# ne5044_emulator.net
KiCad netlist of a schematic drawn in EAGLE
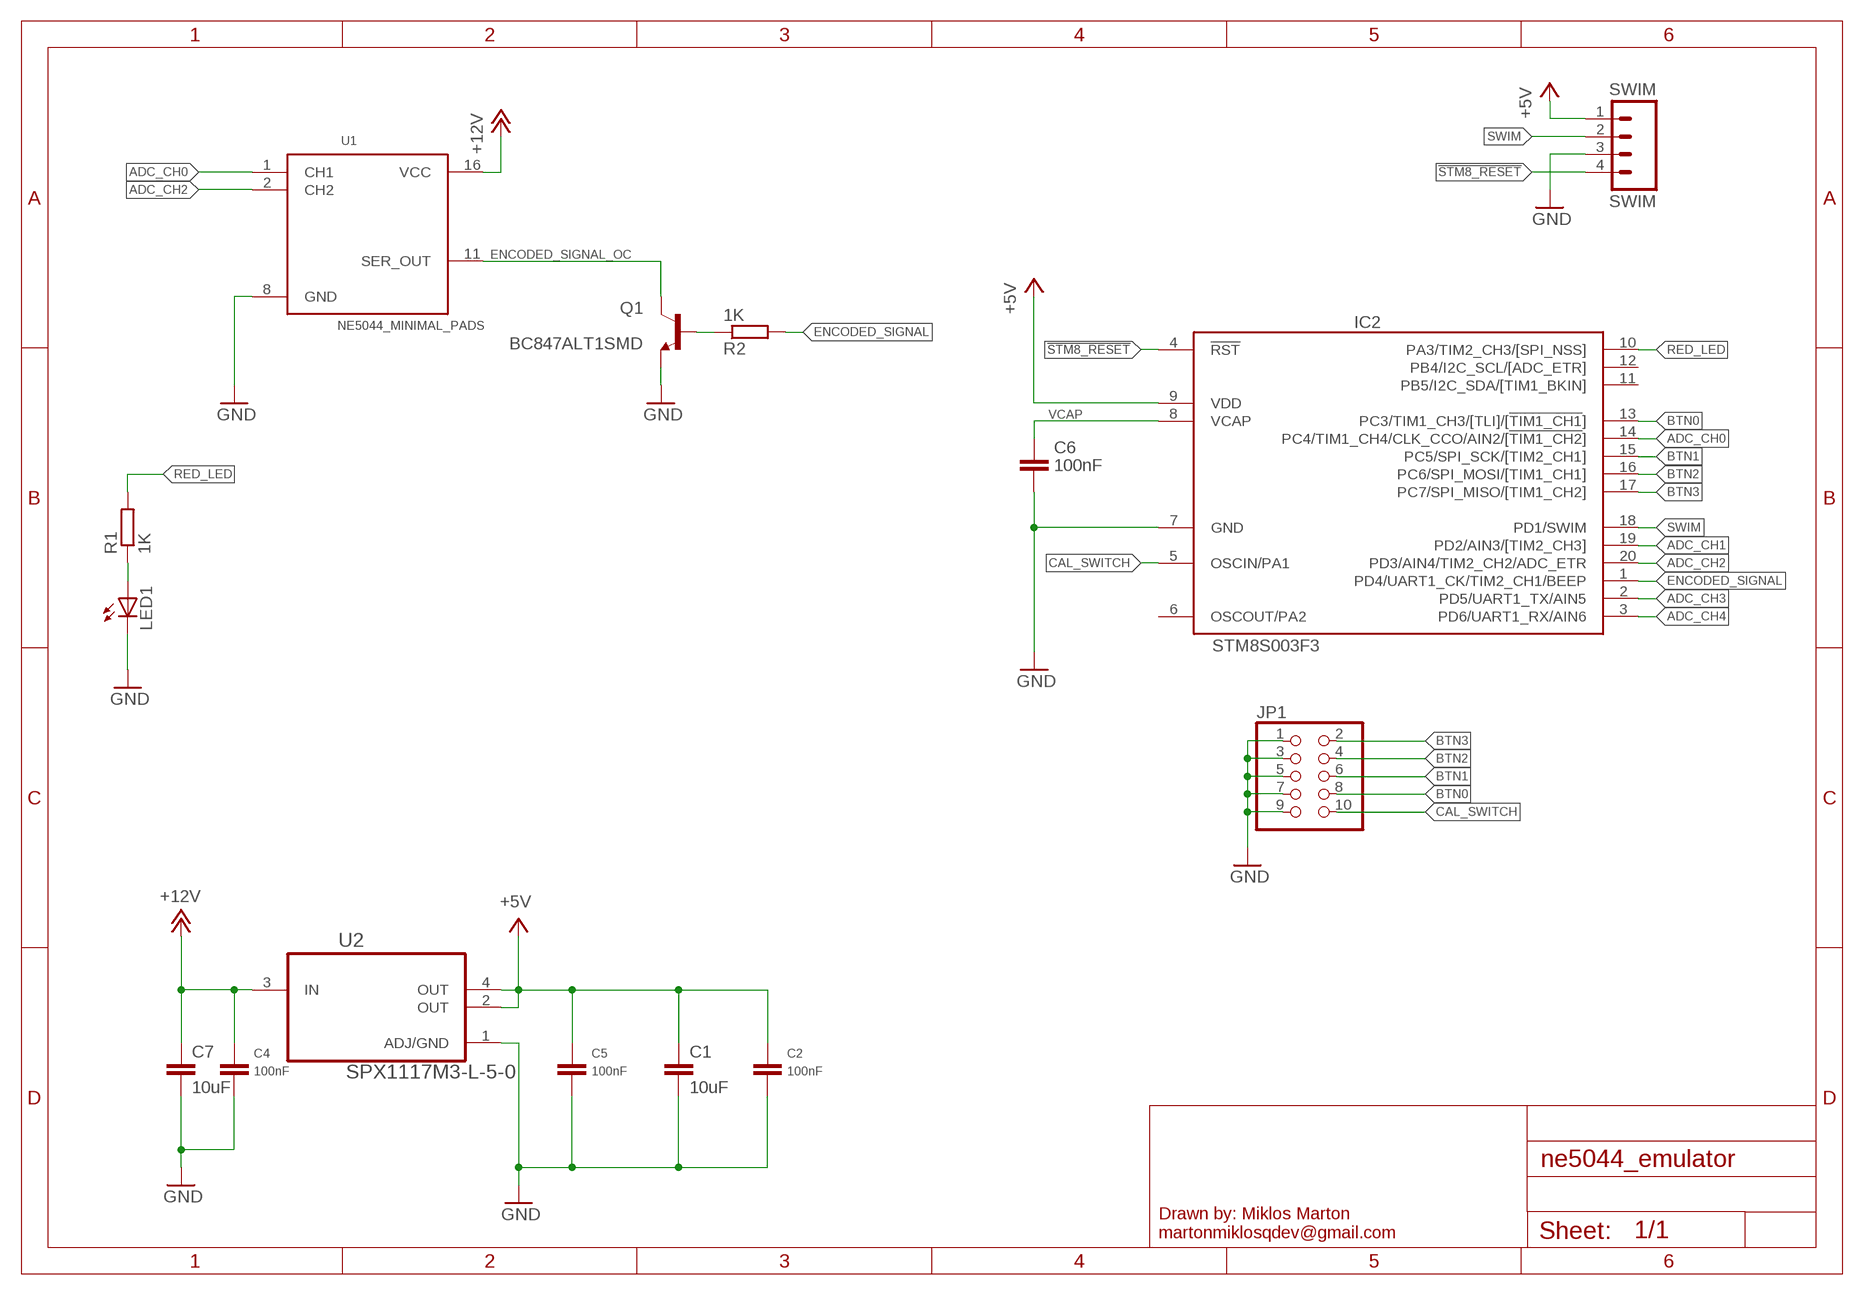
[diagram p0: schematic, sheet 1]

(export (version "E")
  (design (tool "Eeschema 10.0.6"))
  (components
    (comp (ref "C1")
      (value "10uF")
      (footprint "eagle-import:C0805")
      (libsource (lib "eagle-import") (part "C-EUC0805"))
    )
    (comp (ref "C2")
      (value "100nF")
      (footprint "eagle-import:C0603K")
      (libsource (lib "eagle-import") (part "C-EUC0603K"))
    )
    (comp (ref "C4")
      (value "100nF")
      (footprint "eagle-import:C0603K")
      (libsource (lib "eagle-import") (part "C-EUC0603K"))
    )
    (comp (ref "C5")
      (value "100nF")
      (footprint "eagle-import:C0603K")
      (libsource (lib "eagle-import") (part "C-EUC0603K"))
    )
    (comp (ref "C6")
      (value "100nF")
      (footprint "eagle-import:C0603")
      (libsource (lib "eagle-import") (part "C-EUC0603"))
    )
    (comp (ref "C7")
      (value "10uF")
      (footprint "eagle-import:C0805")
      (libsource (lib "eagle-import") (part "C-EUC0805"))
    )
    (comp (ref "IC2")
      (value "STM8S003F3")
      (footprint "eagle-import:TSSOP20")
      (libsource (lib "eagle-import") (part "STM8S003F3"))
    )
    (comp (ref "JP1")
      (value "PINHD-2X5")
      (footprint "eagle-import:2X05")
      (libsource (lib "eagle-import") (part "PINHD-2X5"))
    )
    (comp (ref "LED1")
      (value "LEDCHIP-LED0603")
      (footprint "eagle-import:CHIP-LED0603")
      (libsource (lib "eagle-import") (part "LEDCHIP-LED0603"))
    )
    (comp (ref "Q1")
      (value "BC847ALT1SMD")
      (footprint "eagle-import:SOT23")
      (libsource (lib "eagle-import") (part "BC847SMDALT1"))
    )
    (comp (ref "R1")
      (value "1K")
      (footprint "eagle-import:R0603")
      (libsource (lib "eagle-import") (part "R-EU_R0603"))
    )
    (comp (ref "R2")
      (value "1K")
      (footprint "eagle-import:R0603")
      (libsource (lib "eagle-import") (part "R-EU_R0603"))
    )
    (comp (ref "SWIM")
      (value "SWIM")
      (footprint "eagle-import:1X04-1.27MM")
      (libsource (lib "eagle-import") (part "M041.27MM"))
    )
    (comp (ref "U1")
      (value "NE5044_MINIMAL_PADS")
      (footprint "eagle-import:DIL16_MINIMAL_PADS_FOR_NE5044")
      (libsource (lib "eagle-import") (part "NE5044_MINIMAL_PADS"))
    )
    (comp (ref "U2")
      (value "SPX1117M3-L-5-0")
      (footprint "eagle-import:SOT230P696X180-4N")
      (fields (field (name "MPN") "LM1117MP-ADJ"))
      (libsource (lib "eagle-import") (part "LM1117MP-ADJ"))
    )
  )
  (nets
    (net (code "1") (name "+5V") (class "Default")
      (node (ref "C1") (pin "1") (pinfunction "1_1") (pintype "passive"))
      (node (ref "C2") (pin "1") (pinfunction "1_1") (pintype "passive"))
      (node (ref "C5") (pin "1") (pinfunction "1_1") (pintype "passive"))
      (node (ref "IC2") (pin "9") (pinfunction "VDD_9") (pintype "power_in"))
      (node (ref "SWIM") (pin "1") (pinfunction "1_1") (pintype "passive"))
      (node (ref "U2") (pin "2") (pinfunction "OUT_2") (pintype "passive"))
      (node (ref "U2") (pin "4") (pinfunction "OUT_4") (pintype "passive"))
    )
    (net (code "2") (name "+12V") (class "Default")
      (node (ref "C4") (pin "1") (pinfunction "1_1") (pintype "passive"))
      (node (ref "C7") (pin "1") (pinfunction "1_1") (pintype "passive"))
      (node (ref "U1") (pin "16") (pinfunction "VCC_16") (pintype "passive"))
      (node (ref "U2") (pin "3") (pinfunction "IN_3") (pintype "input"))
    )
    (net (code "3") (name "/ENCODED_SIGNAL_OC") (class "Default")
      (node (ref "Q1") (pin "3") (pinfunction "C_3") (pintype "passive"))
      (node (ref "U1") (pin "11") (pinfunction "SER_OUT_11") (pintype "bidirectional"))
    )
    (net (code "4") (name "/VCAP") (class "Default")
      (node (ref "C6") (pin "1") (pinfunction "1_1") (pintype "passive"))
      (node (ref "IC2") (pin "8") (pinfunction "VCAP_8") (pintype "power_in"))
    )
    (net (code "5") (name "/~{STM8_RESET}") (class "Default")
      (node (ref "IC2") (pin "4") (pinfunction "~{RST}_4") (pintype "input"))
      (node (ref "SWIM") (pin "4") (pinfunction "4_4") (pintype "passive"))
    )
    (net (code "6") (name "ADC_CH0") (class "Default")
      (node (ref "IC2") (pin "14") (pinfunction "PC4/TIM1_CH4/CLK_CCO/AIN2/[~{TIM1_CH2}]_14") (pintype "bidirectional"))
      (node (ref "U1") (pin "1") (pinfunction "CH1_1") (pintype "input"))
    )
    (net (code "7") (name "ADC_CH1") (class "Default")
      (node (ref "IC2") (pin "19") (pinfunction "PD2/AIN3/[TIM2_CH3]_19") (pintype "bidirectional"))
    )
    (net (code "8") (name "ADC_CH2") (class "Default")
      (node (ref "IC2") (pin "20") (pinfunction "PD3/AIN4/TIM2_CH2/ADC_ETR_20") (pintype "bidirectional"))
      (node (ref "U1") (pin "2") (pinfunction "CH2_2") (pintype "input"))
    )
    (net (code "9") (name "ADC_CH3") (class "Default")
      (node (ref "IC2") (pin "2") (pinfunction "PD5/UART1_TX/AIN5_2") (pintype "bidirectional"))
    )
    (net (code "10") (name "ADC_CH4") (class "Default")
      (node (ref "IC2") (pin "3") (pinfunction "PD6/UART1_RX/AIN6_3") (pintype "bidirectional"))
    )
    (net (code "11") (name "BTN0") (class "Default")
      (node (ref "IC2") (pin "13") (pinfunction "PC3/TIM1_CH3/[TLI]/[~{TIM1_CH1}]_13") (pintype "bidirectional"))
      (node (ref "JP1") (pin "8") (pinfunction "8_8") (pintype "passive"))
    )
    (net (code "12") (name "BTN1") (class "Default")
      (node (ref "IC2") (pin "15") (pinfunction "PC5/SPI_SCK/[TIM2_CH1]_15") (pintype "bidirectional"))
      (node (ref "JP1") (pin "6") (pinfunction "6_6") (pintype "passive"))
    )
    (net (code "13") (name "BTN2") (class "Default")
      (node (ref "IC2") (pin "16") (pinfunction "PC6/SPI_MOSI/[TIM1_CH1]_16") (pintype "bidirectional"))
      (node (ref "JP1") (pin "4") (pinfunction "4_4") (pintype "passive"))
    )
    (net (code "14") (name "BTN3") (class "Default")
      (node (ref "IC2") (pin "17") (pinfunction "PC7/SPI_MISO/[TIM1_CH2]_17") (pintype "bidirectional"))
      (node (ref "JP1") (pin "2") (pinfunction "2_2") (pintype "passive"))
    )
    (net (code "15") (name "CAL_SWITCH") (class "Default")
      (node (ref "IC2") (pin "5") (pinfunction "OSCIN/PA1_5") (pintype "bidirectional"))
      (node (ref "JP1") (pin "10") (pinfunction "10_10") (pintype "passive"))
    )
    (net (code "16") (name "ENCODED_SIGNAL") (class "Default")
      (node (ref "IC2") (pin "1") (pinfunction "PD4/UART1_CK/TIM2_CH1/BEEP_1") (pintype "bidirectional"))
      (node (ref "R2") (pin "2") (pinfunction "2_2") (pintype "passive"))
    )
    (net (code "17") (name "GND") (class "Default")
      (node (ref "C1") (pin "2") (pinfunction "2_2") (pintype "passive"))
      (node (ref "C2") (pin "2") (pinfunction "2_2") (pintype "passive"))
      (node (ref "C4") (pin "2") (pinfunction "2_2") (pintype "passive"))
      (node (ref "C5") (pin "2") (pinfunction "2_2") (pintype "passive"))
      (node (ref "C6") (pin "2") (pinfunction "2_2") (pintype "passive"))
      (node (ref "C7") (pin "2") (pinfunction "2_2") (pintype "passive"))
      (node (ref "IC2") (pin "7") (pinfunction "GND_7") (pintype "power_in"))
      (node (ref "JP1") (pin "1") (pinfunction "1_1") (pintype "passive"))
      (node (ref "JP1") (pin "3") (pinfunction "3_3") (pintype "passive"))
      (node (ref "JP1") (pin "5") (pinfunction "5_5") (pintype "passive"))
      (node (ref "JP1") (pin "7") (pinfunction "7_7") (pintype "passive"))
      (node (ref "JP1") (pin "9") (pinfunction "9_9") (pintype "passive"))
      (node (ref "LED1") (pin "C") (pinfunction "C_C") (pintype "passive"))
      (node (ref "Q1") (pin "2") (pinfunction "E_2") (pintype "passive"))
      (node (ref "SWIM") (pin "3") (pinfunction "3_3") (pintype "passive"))
      (node (ref "U1") (pin "8") (pinfunction "GND_8") (pintype "passive"))
      (node (ref "U2") (pin "1") (pinfunction "ADJ/GND_1") (pintype "passive"))
    )
    (net (code "18") (name "Net-(LED1-PadA)") (class "Default")
      (node (ref "LED1") (pin "A") (pinfunction "A_A") (pintype "passive"))
      (node (ref "R1") (pin "1") (pinfunction "1_1") (pintype "passive"))
    )
    (net (code "19") (name "Net-(Q1-B)") (class "Default")
      (node (ref "Q1") (pin "1") (pinfunction "B_1") (pintype "passive"))
      (node (ref "R2") (pin "1") (pinfunction "1_1") (pintype "passive"))
    )
    (net (code "20") (name "RED_LED") (class "Default")
      (node (ref "IC2") (pin "10") (pinfunction "PA3/TIM2_CH3/[SPI_NSS]_10") (pintype "bidirectional"))
      (node (ref "R1") (pin "2") (pinfunction "2_2") (pintype "passive"))
    )
    (net (code "21") (name "SWIM") (class "Default")
      (node (ref "IC2") (pin "18") (pinfunction "PD1/SWIM_18") (pintype "bidirectional"))
      (node (ref "SWIM") (pin "2") (pinfunction "2_2") (pintype "passive"))
    )
    (net (code "22") (name "unconnected-(IC2-OSCOUT{slash}PA2-Pad6)") (class "Default")
      (node (ref "IC2") (pin "6") (pinfunction "OSCOUT/PA2_6") (pintype "bidirectional"))
    )
    (net (code "23") (name "unconnected-(IC2-PB4{slash}I2C_SCL{slash}[ADC_ETR]-Pad12)") (class "Default")
      (node (ref "IC2") (pin "12") (pinfunction "PB4/I2C_SCL/[ADC_ETR]_12") (pintype "bidirectional"))
    )
    (net (code "24") (name "unconnected-(IC2-PB5{slash}I2C_SDA{slash}[TIM1_BKIN]-Pad11)") (class "Default")
      (node (ref "IC2") (pin "11") (pinfunction "PB5/I2C_SDA/[TIM1_BKIN]_11") (pintype "bidirectional"))
    )
  )
)
